# Safety.net
KiCad netlist of a schematic drawn in Altium Designer
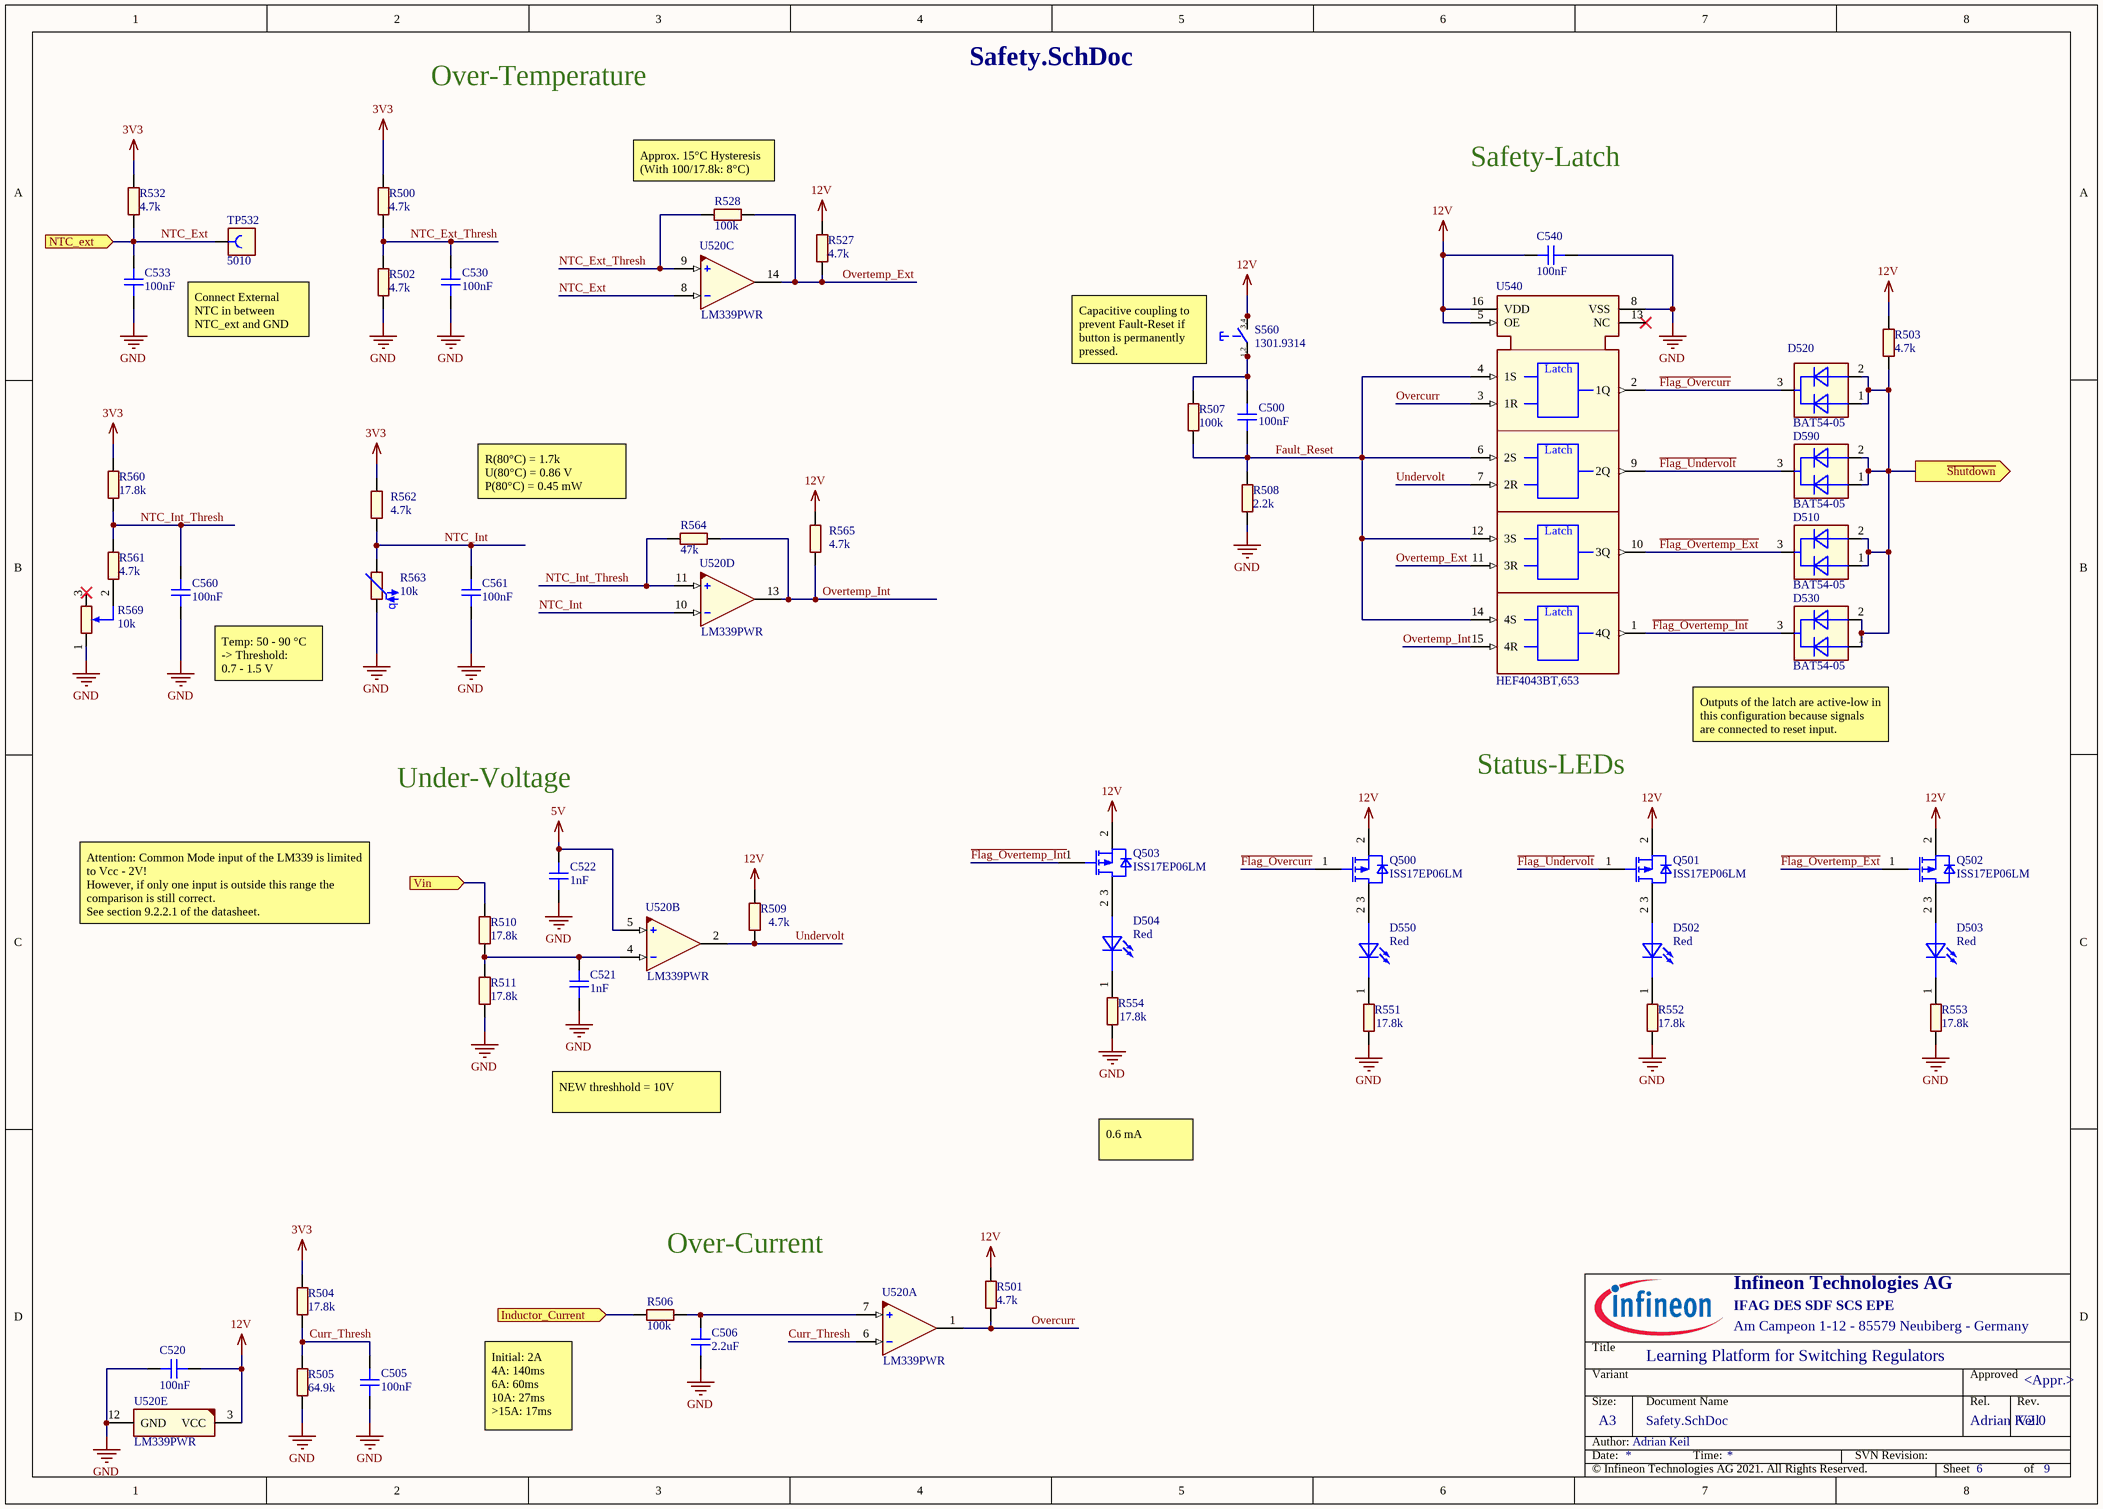
[diagram p0: Safety.SchDoc]

(export (version "E")
  (design (tool "Eeschema 10.0.6"))
  (components
    (comp (ref "C500")
      (value "100nF")
      (footprint "CAPC3216X125N-0")
      (description "CAP / CERA / 100nF / 50V / 10% / X7R (EIA) / -55°C to 125°C / 1206(3216) / SMD / -")
      (fields (field (name "LEGACY PARTNUMBER") "CAP01005660") (field (name "MANUFACTURER") "MuRata"))
      (libsource (lib "PCBLibraryData") (part "CAP-SGL-STD-02P_00000001"))
    )
    (comp (ref "C505")
      (value "100nF")
      (footprint "CAPC3216X125N-0")
      (description "CAP / CERA / 100nF / 50V / 10% / X7R (EIA) / -55°C to 125°C / 1206(3216) / SMD / -")
      (fields (field (name "LEGACY PARTNUMBER") "CAP01005660") (field (name "MANUFACTURER") "MuRata"))
      (libsource (lib "PCBLibraryData") (part "CAP-SGL-STD-02P_00000001"))
    )
    (comp (ref "C506")
      (value "2.2uF")
      (footprint "CAPC3216X70N")
      (description "CAP / CERA / 2.2uF / 25V / 10% / X5R (EIA) / -55°C to 85°C / 1206(3216) / SMD / -")
      (fields (field (name "LEGACY PARTNUMBER") "CAP01005015") (field (name "MANUFACTURER") "MuRata"))
      (libsource (lib "PCBLibraryData") (part "CAP-SGL-STD-02P_00000001"))
    )
    (comp (ref "C520")
      (value "100nF")
      (footprint "CAPC3216X125N-0")
      (description "CAP / CERA / 100nF / 50V / 10% / X7R (EIA) / -55°C to 125°C / 1206(3216) / SMD / -")
      (fields (field (name "LEGACY PARTNUMBER") "CAP01005660") (field (name "MANUFACTURER") "MuRata"))
      (libsource (lib "PCBLibraryData") (part "CAP-SGL-STD-02P_00000001"))
    )
    (comp (ref "C521")
      (value "1nF")
      (footprint "CAPC3216X95N")
      (description "CAP / CERA / 1nF / 50V / 10% / X7R (EIA) / -55°C to 125°C / 1206(3216) / SMD / -")
      (fields (field (name "LEGACY PARTNUMBER") "CAP01005183") (field (name "MANUFACTURER") "MuRata"))
      (libsource (lib "PCBLibraryData") (part "CAP-SGL-STD-02P_00000001"))
    )
    (comp (ref "C522")
      (value "1nF")
      (footprint "CAPC3216X95N")
      (description "CAP / CERA / 1nF / 50V / 10% / X7R (EIA) / -55°C to 125°C / 1206(3216) / SMD / -")
      (fields (field (name "LEGACY PARTNUMBER") "CAP01005183") (field (name "MANUFACTURER") "MuRata"))
      (libsource (lib "PCBLibraryData") (part "CAP-SGL-STD-02P_00000001"))
    )
    (comp (ref "C530")
      (value "100nF")
      (footprint "CAPC3216X125N-0")
      (description "CAP / CERA / 100nF / 50V / 10% / X7R (EIA) / -55°C to 125°C / 1206(3216) / SMD / -")
      (fields (field (name "LEGACY PARTNUMBER") "CAP01005660") (field (name "MANUFACTURER") "MuRata"))
      (libsource (lib "PCBLibraryData") (part "CAP-SGL-STD-02P_00000001"))
    )
    (comp (ref "C533")
      (value "100nF")
      (footprint "CAPC3216X125N-0")
      (description "CAP / CERA / 100nF / 50V / 10% / X7R (EIA) / -55°C to 125°C / 1206(3216) / SMD / -")
      (fields (field (name "LEGACY PARTNUMBER") "CAP01005660") (field (name "MANUFACTURER") "MuRata"))
      (libsource (lib "PCBLibraryData") (part "CAP-SGL-STD-02P_00000001"))
    )
    (comp (ref "C540")
      (value "100nF")
      (footprint "CAPC3216X125N-0")
      (description "CAP / CERA / 100nF / 50V / 10% / X7R (EIA) / -55°C to 125°C / 1206(3216) / SMD / -")
      (fields (field (name "LEGACY PARTNUMBER") "CAP01005660") (field (name "MANUFACTURER") "MuRata"))
      (libsource (lib "PCBLibraryData") (part "CAP-SGL-STD-02P_00000001"))
    )
    (comp (ref "C560")
      (value "100nF")
      (footprint "CAPC3216X125N-0")
      (description "CAP / CERA / 100nF / 50V / 10% / X7R (EIA) / -55°C to 125°C / 1206(3216) / SMD / -")
      (fields (field (name "LEGACY PARTNUMBER") "CAP01005660") (field (name "MANUFACTURER") "MuRata"))
      (libsource (lib "PCBLibraryData") (part "CAP-SGL-STD-02P_00000001"))
    )
    (comp (ref "C561")
      (value "100nF")
      (footprint "CAPC3216X125N-0")
      (description "CAP / CERA / 100nF / 50V / 10% / X7R (EIA) / -55°C to 125°C / 1206(3216) / SMD / -")
      (fields (field (name "LEGACY PARTNUMBER") "CAP01005660") (field (name "MANUFACTURER") "MuRata"))
      (libsource (lib "PCBLibraryData") (part "CAP-SGL-STD-02P_00000001"))
    )
    (comp (ref "D502")
      (value "Red")
      (footprint "LEDSC160X80X80-2N-1")
      (description "WL-SMCW SMT Mono-color Chip LED Waterclear, Red,630nm")
      (fields (field (name "MANUFACTURER") "Wurth Elektronik"))
      (libsource (lib "PCBLibraryData") (part "d_led_a"))
    )
    (comp (ref "D503")
      (value "Red")
      (footprint "LEDSC160X80X80-2N-1")
      (description "WL-SMCW SMT Mono-color Chip LED Waterclear, Red,630nm")
      (fields (field (name "MANUFACTURER") "Wurth Elektronik"))
      (libsource (lib "PCBLibraryData") (part "d_led_a"))
    )
    (comp (ref "D504")
      (value "Red")
      (footprint "LEDSC160X80X80-2N-1")
      (description "WL-SMCW SMT Mono-color Chip LED Waterclear, Red,630nm")
      (fields (field (name "MANUFACTURER") "Wurth Elektronik"))
      (libsource (lib "PCBLibraryData") (part "d_led_a"))
    )
    (comp (ref "D510")
      (value "BAT54-05")
      (footprint "SOT95P240X110-3N-1-V")
      (description "Silicon Schottky Diode, LS(nH) 1.8, VR 30V")
      (fields
        (field (name "LEGACY PARTNUMBER") "IFX01401370")
        (field (name "MANUFACTURER") "Infineon Technologies")
      )
      (libsource (lib "PCBLibraryData") (part "d_dual_a1a2c3_3p"))
    )
    (comp (ref "D520")
      (value "BAT54-05")
      (footprint "SOT95P240X110-3N-1-V")
      (description "Silicon Schottky Diode, LS(nH) 1.8, VR 30V")
      (fields
        (field (name "LEGACY PARTNUMBER") "IFX01401370")
        (field (name "MANUFACTURER") "Infineon Technologies")
      )
      (libsource (lib "PCBLibraryData") (part "d_dual_a1a2c3_3p"))
    )
    (comp (ref "D530")
      (value "BAT54-05")
      (footprint "SOT95P240X110-3N-1-V")
      (description "Silicon Schottky Diode, LS(nH) 1.8, VR 30V")
      (fields
        (field (name "LEGACY PARTNUMBER") "IFX01401370")
        (field (name "MANUFACTURER") "Infineon Technologies")
      )
      (libsource (lib "PCBLibraryData") (part "d_dual_a1a2c3_3p"))
    )
    (comp (ref "D550")
      (value "Red")
      (footprint "LEDSC160X80X80-2N-1")
      (description "WL-SMCW SMT Mono-color Chip LED Waterclear, Red,630nm")
      (fields (field (name "MANUFACTURER") "Wurth Elektronik"))
      (libsource (lib "PCBLibraryData") (part "d_led_a"))
    )
    (comp (ref "D590")
      (value "BAT54-05")
      (footprint "SOT95P240X110-3N-1-V")
      (description "Silicon Schottky Diode, LS(nH) 1.8, VR 30V")
      (fields
        (field (name "LEGACY PARTNUMBER") "IFX01401370")
        (field (name "MANUFACTURER") "Infineon Technologies")
      )
      (libsource (lib "PCBLibraryData") (part "d_dual_a1a2c3_3p"))
    )
    (comp (ref "Q500")
      (value "ISS17EP06LM")
      (footprint "SOT95P240X110-3N-1-V")
      (description "OptiMOSTM Small Signal Transistor, -60 V")
      (fields (field (name "MANUFACTURER") "Infineon Technologies"))
      (libsource (lib "PCBLibraryData") (part "igfet_p_ch_enh_dio_1g2s3d_3p"))
    )
    (comp (ref "Q501")
      (value "ISS17EP06LM")
      (footprint "SOT95P240X110-3N-1-V")
      (description "OptiMOSTM Small Signal Transistor, -60 V")
      (fields (field (name "MANUFACTURER") "Infineon Technologies"))
      (libsource (lib "PCBLibraryData") (part "igfet_p_ch_enh_dio_1g2s3d_3p"))
    )
    (comp (ref "Q502")
      (value "ISS17EP06LM")
      (footprint "SOT95P240X110-3N-1-V")
      (description "OptiMOSTM Small Signal Transistor, -60 V")
      (fields (field (name "MANUFACTURER") "Infineon Technologies"))
      (libsource (lib "PCBLibraryData") (part "igfet_p_ch_enh_dio_1g2s3d_3p"))
    )
    (comp (ref "Q503")
      (value "ISS17EP06LM")
      (footprint "SOT95P240X110-3N-1-V")
      (description "OptiMOSTM Small Signal Transistor, -60 V")
      (fields (field (name "MANUFACTURER") "Infineon Technologies"))
      (libsource (lib "PCBLibraryData") (part "igfet_p_ch_enh_dio_1g2s3d_3p"))
    )
    (comp (ref "R500")
      (value "4.7k")
      (footprint "RESC3216X60N")
      (description "RES / STD / 4.7k / 250mW / 1% / 100ppm/K / -55°C to 155°C / 1206(3216) / SMD / -")
      (fields (field (name "LEGACY PARTNUMBER") "RES01802819") (field (name "MANUFACTURER") "Vishay"))
      (libsource (lib "PCBLibraryData") (part "RES-SGL-STD-02P_00000006"))
    )
    (comp (ref "R501")
      (value "4.7k")
      (footprint "RESC3216X60N")
      (description "RES / STD / 4.7k / 250mW / 1% / 100ppm/K / -55°C to 155°C / 1206(3216) / SMD / -")
      (fields (field (name "LEGACY PARTNUMBER") "RES01802819") (field (name "MANUFACTURER") "Vishay"))
      (libsource (lib "PCBLibraryData") (part "RES-SGL-STD-02P_00000006"))
    )
    (comp (ref "R502")
      (value "4.7k")
      (footprint "RESC3216X60N")
      (description "RES / STD / 4.7k / 250mW / 1% / 100ppm/K / -55°C to 155°C / 1206(3216) / SMD / -")
      (fields (field (name "LEGACY PARTNUMBER") "RES01802819") (field (name "MANUFACTURER") "Vishay"))
      (libsource (lib "PCBLibraryData") (part "RES-SGL-STD-02P_00000006"))
    )
    (comp (ref "R503")
      (value "4.7k")
      (footprint "RESC3216X60N")
      (description "RES / STD / 4.7k / 250mW / 1% / 100ppm/K / -55°C to 155°C / 1206(3216) / SMD / -")
      (fields (field (name "LEGACY PARTNUMBER") "RES01802819") (field (name "MANUFACTURER") "Vishay"))
      (libsource (lib "PCBLibraryData") (part "RES-SGL-STD-02P_00000006"))
    )
    (comp (ref "R504")
      (value "17.8k")
      (footprint "RESC3216X60N")
      (description "RES / STD / 17.8k / 250mW / 1% / 100ppm/K / -55°C to 155°C / 1206(3216) / SMD / -")
      (fields (field (name "LEGACY PARTNUMBER") "RES01802883") (field (name "MANUFACTURER") "Vishay"))
      (libsource (lib "PCBLibraryData") (part "RES-SGL-STD-02P_00000006"))
    )
    (comp (ref "R505")
      (value "64.9k")
      (footprint "RESC3216X60N")
      (description "RES / STD / 64.9k / 250mW / 1% / 100ppm/K / -55°C to 155°C / 1206(3216) / SMD / -")
      (fields (field (name "LEGACY PARTNUMBER") "RES01802950") (field (name "MANUFACTURER") "Vishay"))
      (libsource (lib "PCBLibraryData") (part "RES-SGL-STD-02P_00000006"))
    )
    (comp (ref "R506")
      (value "100k")
      (footprint "RESC3216X60N")
      (description "RES / STD / 100k / 250mW / 1% / 100ppm/K / -55°C to 155°C / 1206(3216) / SMD / -")
      (fields (field (name "LEGACY PARTNUMBER") "RES01802971") (field (name "MANUFACTURER") "Vishay"))
      (libsource (lib "") (part "RES-SGL-STD-02P_00000006_3"))
    )
    (comp (ref "R507")
      (value "100k")
      (footprint "RESC3216X60N")
      (description "RES / STD / 100k / 250mW / 1% / 100ppm/K / -55°C to 155°C / 1206(3216) / SMD / -")
      (fields (field (name "LEGACY PARTNUMBER") "RES01802971") (field (name "MANUFACTURER") "Vishay"))
      (libsource (lib "PCBLibraryData") (part "RES-SGL-STD-02P_00000006"))
    )
    (comp (ref "R508")
      (value "2.2k")
      (footprint "RESC3216X60N")
      (description "RES / STD / 2.2k / 250mW / 1% / 100ppm/K / -55°C to 155°C / 1206(3216) / SMD / -")
      (fields (field (name "LEGACY PARTNUMBER") "RES01802779") (field (name "MANUFACTURER") "Vishay"))
      (libsource (lib "") (part "RES-SGL-STD-02P_00000006_2"))
    )
    (comp (ref "R509")
      (value "4.7k")
      (footprint "RESC3216X60N")
      (description "RES / STD / 4.7k / 250mW / 1% / 100ppm/K / -55°C to 155°C / 1206(3216) / SMD / -")
      (fields (field (name "LEGACY PARTNUMBER") "RES01802819") (field (name "MANUFACTURER") "Vishay"))
      (libsource (lib "PCBLibraryData") (part "RES-SGL-STD-02P_00000006"))
    )
    (comp (ref "R510")
      (value "17.8k")
      (footprint "RESC3216X60N")
      (description "RES / STD / 17.8k / 250mW / 1% / 100ppm/K / -55°C to 155°C / 1206(3216) / SMD / -")
      (fields (field (name "LEGACY PARTNUMBER") "RES01802883") (field (name "MANUFACTURER") "Vishay"))
      (libsource (lib "") (part "RES-SGL-STD-02P_00000006_2"))
    )
    (comp (ref "R511")
      (value "17.8k")
      (footprint "RESC3216X60N")
      (description "RES / STD / 17.8k / 250mW / 1% / 100ppm/K / -55°C to 155°C / 1206(3216) / SMD / -")
      (fields (field (name "LEGACY PARTNUMBER") "RES01802883") (field (name "MANUFACTURER") "Vishay"))
      (libsource (lib "PCBLibraryData") (part "RES-SGL-STD-02P_00000006"))
    )
    (comp (ref "R527")
      (value "4.7k")
      (footprint "RESC3216X60N")
      (description "RES / STD / 4.7k / 250mW / 1% / 100ppm/K / -55°C to 155°C / 1206(3216) / SMD / -")
      (fields (field (name "LEGACY PARTNUMBER") "RES01802819") (field (name "MANUFACTURER") "Vishay"))
      (libsource (lib "PCBLibraryData") (part "RES-SGL-STD-02P_00000006"))
    )
    (comp (ref "R528")
      (value "100k")
      (footprint "RESC3216X60N")
      (description "RES / STD / 100k / 250mW / 1% / 100ppm/K / -55°C to 155°C / 1206(3216) / SMD / -")
      (fields (field (name "LEGACY PARTNUMBER") "RES01802971") (field (name "MANUFACTURER") "Vishay"))
      (libsource (lib "") (part "RES-SGL-STD-02P_00000006_1"))
    )
    (comp (ref "R532")
      (value "4.7k")
      (footprint "RESC3216X60N")
      (description "RES / STD / 4.7k / 250mW / 1% / 100ppm/K / -55°C to 155°C / 1206(3216) / SMD / -")
      (fields (field (name "LEGACY PARTNUMBER") "RES01802819") (field (name "MANUFACTURER") "Vishay"))
      (libsource (lib "PCBLibraryData") (part "RES-SGL-STD-02P_00000006"))
    )
    (comp (ref "R551")
      (value "17.8k")
      (footprint "RESC3216X60N")
      (description "RES / STD / 17.8k / 250mW / 1% / 100ppm/K / -55°C to 155°C / 1206(3216) / SMD / -")
      (fields (field (name "LEGACY PARTNUMBER") "RES01802883") (field (name "MANUFACTURER") "Vishay"))
      (libsource (lib "") (part "RES-SGL-STD-02P_00000006_2"))
    )
    (comp (ref "R552")
      (value "17.8k")
      (footprint "RESC3216X60N")
      (description "RES / STD / 17.8k / 250mW / 1% / 100ppm/K / -55°C to 155°C / 1206(3216) / SMD / -")
      (fields (field (name "LEGACY PARTNUMBER") "RES01802883") (field (name "MANUFACTURER") "Vishay"))
      (libsource (lib "PCBLibraryData") (part "RES-SGL-STD-02P_00000006"))
    )
    (comp (ref "R553")
      (value "17.8k")
      (footprint "RESC3216X60N")
      (description "RES / STD / 17.8k / 250mW / 1% / 100ppm/K / -55°C to 155°C / 1206(3216) / SMD / -")
      (fields (field (name "LEGACY PARTNUMBER") "RES01802883") (field (name "MANUFACTURER") "Vishay"))
      (libsource (lib "PCBLibraryData") (part "RES-SGL-STD-02P_00000006"))
    )
    (comp (ref "R554")
      (value "17.8k")
      (footprint "RESC3216X60N")
      (description "RES / STD / 17.8k / 250mW / 1% / 100ppm/K / -55°C to 155°C / 1206(3216) / SMD / -")
      (fields (field (name "LEGACY PARTNUMBER") "RES01802883") (field (name "MANUFACTURER") "Vishay"))
      (libsource (lib "") (part "RES-SGL-STD-02P_00000006_2"))
    )
    (comp (ref "R560")
      (value "17.8k")
      (footprint "RESC3216X60N")
      (description "RES / STD / 17.8k / 250mW / 1% / 100ppm/K / -55°C to 155°C / 1206(3216) / SMD / -")
      (fields (field (name "LEGACY PARTNUMBER") "RES01802883") (field (name "MANUFACTURER") "Vishay"))
      (libsource (lib "") (part "RES-SGL-STD-02P_00000006_2"))
    )
    (comp (ref "R561")
      (value "4.7k")
      (footprint "RESC3216X60N")
      (description "RES / STD / 4.7k / 250mW / 1% / 100ppm/K / -55°C to 155°C / 1206(3216) / SMD / -")
      (fields (field (name "LEGACY PARTNUMBER") "RES01802819") (field (name "MANUFACTURER") "Vishay"))
      (libsource (lib "PCBLibraryData") (part "RES-SGL-STD-02P_00000006"))
    )
    (comp (ref "R562")
      (value "4.7k")
      (footprint "RESC3216X60N")
      (description "RES / STD / 4.7k / 250mW / 1% / 100ppm/K / -55°C to 155°C / 1206(3216) / SMD / -")
      (fields (field (name "LEGACY PARTNUMBER") "RES01802819") (field (name "MANUFACTURER") "Vishay"))
      (libsource (lib "PCBLibraryData") (part "RES-SGL-STD-02P_00000006"))
    )
    (comp (ref "R563")
      (value "10k")
      (footprint "RESC1608X95N-1")
      (description "RES / NTC / 10k / 100mW / 1% / - / -40°C to 125°C / 0603(1608) / SMD / -")
      (fields (field (name "LEGACY PARTNUMBER") "RES01806219") (field (name "MANUFACTURER") "MuRata"))
      (libsource (lib "PCBLibraryData") (part "RES-SGL-NTC-02P_00000007"))
    )
    (comp (ref "R564")
      (value "47k")
      (footprint "RESC3216X60N")
      (description "RES / STD / 47k / 250mW / 1% / 100ppm/K / -55°C to 155°C / 1206(3216) / SMD / -")
      (fields (field (name "LEGACY PARTNUMBER") "RES01802933") (field (name "MANUFACTURER") "Vishay"))
      (libsource (lib "") (part "RES-SGL-STD-02P_00000006_1"))
    )
    (comp (ref "R565")
      (value "4.7k")
      (footprint "RESC3216X60N")
      (description "RES / STD / 4.7k / 250mW / 1% / 100ppm/K / -55°C to 155°C / 1206(3216) / SMD / -")
      (fields (field (name "LEGACY PARTNUMBER") "RES01802819") (field (name "MANUFACTURER") "Vishay"))
      (libsource (lib "PCBLibraryData") (part "RES-SGL-STD-02P_00000006"))
    )
    (comp (ref "R569")
      (value "10k")
      (footprint "POT-SMD-3361P")
      (fields (field (name "MANUFACTURER") "Bourns"))
      (libsource (lib "PCBLibraryData") (part "RES-SGL-VAR-03P_00000026"))
    )
    (comp (ref "S560")
      (value "1301.9314")
      (footprint "SW-SMD-1301.9314")
      (description "Pushbutton Tactile Switch, Single Pole Single Throw, 4 Pins")
      (fields (field (name "LEGACY PARTNUMBER") "CON01500305") (field (name "MANUFACTURER") "Schurter"))
      (libsource (lib "PCBLibraryData") (part "sw_sr_no12_34_4p"))
    )
    (comp (ref "TP532")
      (value "5010")
      (footprint "CON-THT-TP-5010")
      (description "PC Test Point-Multipurpose THT, Red")
      (fields
        (field (name "LEGACY PARTNUMBER") "CON01500529")
        (field (name "MANUFACTURER") "Keystone Electronics Corp.")
      )
      (libsource (lib "PCBLibraryData") (part "connector_1_f"))
    )
    (comp (ref "U520")
      (value "LM339PWR")
      (footprint "SOP65P640X120-14N-1")
      (description "Quad Differential Comparator")
      (fields
        (field (name "LEGACY PARTNUMBER") "IC02600564")
        (field (name "MANUFACTURER") "Texas Instruments")
      )
      (libsource (lib "PCBLibraryData") (part "LM339PWR"))
    )
    (comp (ref "U540")
      (value "HEF4043BT,653")
      (footprint "SOIC127P600X175-16N-6")
      (description "Quad R/S latch with 3-state outputs")
      (fields (field (name "MANUFACTURER") "Nexperia"))
      (libsource (lib "PCBLibraryData") (part "HEF4043B"))
    )
  )
  (nets
    (net (code "1") (name "/Curr_Thresh") (class "Default")
      (node (ref "C505") (pin "2") (pinfunction "2_2") (pintype "passive"))
      (node (ref "R504") (pin "1") (pinfunction "1_1") (pintype "passive"))
      (node (ref "R505") (pin "2") (pinfunction "2_2") (pintype "passive"))
      (node (ref "U520") (pin "6") (pinfunction "1IN_N_6") (pintype "input"))
    )
    (net (code "2") (name "/Fault_Reset") (class "Default")
      (node (ref "C500") (pin "2") (pinfunction "2_2") (pintype "passive"))
      (node (ref "R507") (pin "1") (pinfunction "1_1") (pintype "passive"))
      (node (ref "R508") (pin "1") (pinfunction "1_1") (pintype "passive"))
      (node (ref "U540") (pin "12") (pinfunction "3S_12") (pintype "input"))
      (node (ref "U540") (pin "14") (pinfunction "4S_14") (pintype "input"))
      (node (ref "U540") (pin "4") (pinfunction "1S_4") (pintype "input"))
      (node (ref "U540") (pin "6") (pinfunction "2S_6") (pintype "input"))
    )
    (net (code "3") (name "/Flag_Overcurr") (class "Default")
      (node (ref "D520") (pin "3") (pinfunction "CATHODE_3") (pintype "passive"))
      (node (ref "Q500") (pin "1") (pinfunction "GATE_1") (pintype "passive"))
      (node (ref "U540") (pin "2") (pinfunction "1Q_2") (pintype "output"))
    )
    (net (code "4") (name "/Flag_Overtemp_Ext") (class "Default")
      (node (ref "D510") (pin "3") (pinfunction "CATHODE_3") (pintype "passive"))
      (node (ref "Q502") (pin "1") (pinfunction "GATE_1") (pintype "passive"))
      (node (ref "U540") (pin "10") (pinfunction "3Q_10") (pintype "output"))
    )
    (net (code "5") (name "/Flag_Overtemp_Int") (class "Default")
      (node (ref "D530") (pin "3") (pinfunction "CATHODE_3") (pintype "passive"))
      (node (ref "Q503") (pin "1") (pinfunction "GATE_1") (pintype "passive"))
      (node (ref "U540") (pin "1") (pinfunction "4Q_1") (pintype "output"))
    )
    (net (code "6") (name "/Flag_Undervolt") (class "Default")
      (node (ref "D590") (pin "3") (pinfunction "CATHODE_3") (pintype "passive"))
      (node (ref "Q501") (pin "1") (pinfunction "GATE_1") (pintype "passive"))
      (node (ref "U540") (pin "9") (pinfunction "2Q_9") (pintype "output"))
    )
    (net (code "7") (name "/Inductor_Current") (class "Default")
      (node (ref "R506") (pin "1") (pinfunction "1_1") (pintype "passive"))
    )
    (net (code "8") (name "/NTC_Ext") (class "Default")
      (node (ref "C533") (pin "2") (pinfunction "2_2") (pintype "passive"))
      (node (ref "R532") (pin "1") (pinfunction "1_1") (pintype "passive"))
      (node (ref "TP532") (pin "1") (pinfunction "1_1") (pintype "passive"))
      (node (ref "U520") (pin "8") (pinfunction "3IN_N_8") (pintype "input"))
    )
    (net (code "9") (name "/NTC_Ext_Thresh") (class "Default")
      (node (ref "C530") (pin "2") (pinfunction "2_2") (pintype "passive"))
      (node (ref "R500") (pin "1") (pinfunction "1_1") (pintype "passive"))
      (node (ref "R502") (pin "2") (pinfunction "2_2") (pintype "passive"))
      (node (ref "R528") (pin "2") (pinfunction "2_2") (pintype "passive"))
      (node (ref "U520") (pin "9") (pinfunction "3IN_P_9") (pintype "input"))
    )
    (net (code "10") (name "/NTC_Int") (class "Default")
      (node (ref "C561") (pin "2") (pinfunction "2_2") (pintype "passive"))
      (node (ref "R562") (pin "1") (pinfunction "1_1") (pintype "passive"))
      (node (ref "R563") (pin "2") (pinfunction "2_2") (pintype "passive"))
      (node (ref "U520") (pin "10") (pinfunction "4IN_N_10") (pintype "input"))
    )
    (net (code "11") (name "/NTC_Int_Thresh") (class "Default")
      (node (ref "C560") (pin "2") (pinfunction "2_2") (pintype "passive"))
      (node (ref "R560") (pin "2") (pinfunction "2_2") (pintype "passive"))
      (node (ref "R561") (pin "2") (pinfunction "2_2") (pintype "passive"))
      (node (ref "R564") (pin "2") (pinfunction "2_2") (pintype "passive"))
      (node (ref "U520") (pin "11") (pinfunction "4IN_P_11") (pintype "input"))
    )
    (net (code "12") (name "/Overcurr") (class "Default")
      (node (ref "R501") (pin "1") (pinfunction "1_1") (pintype "passive"))
      (node (ref "U520") (pin "1") (pinfunction "1OUT_1") (pintype "open_collector"))
      (node (ref "U540") (pin "3") (pinfunction "1R_3") (pintype "input"))
    )
    (net (code "13") (name "/Overtemp_Ext") (class "Default")
      (node (ref "R527") (pin "1") (pinfunction "1_1") (pintype "passive"))
      (node (ref "R528") (pin "1") (pinfunction "1_1") (pintype "passive"))
      (node (ref "U520") (pin "14") (pinfunction "3OUT_14") (pintype "open_collector"))
      (node (ref "U540") (pin "11") (pinfunction "3R_11") (pintype "input"))
    )
    (net (code "14") (name "/Overtemp_Int") (class "Default")
      (node (ref "R564") (pin "1") (pinfunction "1_1") (pintype "passive"))
      (node (ref "R565") (pin "1") (pinfunction "1_1") (pintype "passive"))
      (node (ref "U520") (pin "13") (pinfunction "4OUT_13") (pintype "open_collector"))
      (node (ref "U540") (pin "15") (pinfunction "4R_15") (pintype "input"))
    )
    (net (code "15") (name "/Shutdown") (class "Default")
      (node (ref "D510") (pin "1") (pinfunction "ANODE_1_1") (pintype "passive"))
      (node (ref "D510") (pin "2") (pinfunction "ANODE_2_2") (pintype "passive"))
      (node (ref "D520") (pin "1") (pinfunction "ANODE_1_1") (pintype "passive"))
      (node (ref "D520") (pin "2") (pinfunction "ANODE_2_2") (pintype "passive"))
      (node (ref "D530") (pin "1") (pinfunction "ANODE_1_1") (pintype "passive"))
      (node (ref "D530") (pin "2") (pinfunction "ANODE_2_2") (pintype "passive"))
      (node (ref "D590") (pin "1") (pinfunction "ANODE_1_1") (pintype "passive"))
      (node (ref "D590") (pin "2") (pinfunction "ANODE_2_2") (pintype "passive"))
      (node (ref "R503") (pin "1") (pinfunction "1_1") (pintype "passive"))
    )
    (net (code "16") (name "/Undervolt") (class "Default")
      (node (ref "R509") (pin "1") (pinfunction "1_1") (pintype "passive"))
      (node (ref "U520") (pin "2") (pinfunction "2OUT_2") (pintype "open_collector"))
      (node (ref "U540") (pin "7") (pinfunction "2R_7") (pintype "input"))
    )
    (net (code "17") (name "/Vin") (class "Default")
      (node (ref "R510") (pin "1") (pinfunction "1_1") (pintype "passive"))
    )
    (net (code "18") (name "3V3") (class "Default")
      (node (ref "R500") (pin "2") (pinfunction "2_2") (pintype "passive"))
      (node (ref "R504") (pin "2") (pinfunction "2_2") (pintype "passive"))
      (node (ref "R532") (pin "2") (pinfunction "2_2") (pintype "passive"))
      (node (ref "R560") (pin "1") (pinfunction "1_1") (pintype "passive"))
      (node (ref "R562") (pin "2") (pinfunction "2_2") (pintype "passive"))
    )
    (net (code "19") (name "5V") (class "Default")
      (node (ref "C522") (pin "2") (pinfunction "2_2") (pintype "passive"))
      (node (ref "U520") (pin "5") (pinfunction "2IN_P_5") (pintype "input"))
    )
    (net (code "20") (name "12V") (class "Default")
      (node (ref "C520") (pin "1") (pinfunction "1_1") (pintype "passive"))
      (node (ref "C540") (pin "2") (pinfunction "2_2") (pintype "passive"))
      (node (ref "Q500") (pin "2") (pinfunction "SOURCE_2") (pintype "passive"))
      (node (ref "Q501") (pin "2") (pinfunction "SOURCE_2") (pintype "passive"))
      (node (ref "Q502") (pin "2") (pinfunction "SOURCE_2") (pintype "passive"))
      (node (ref "Q503") (pin "2") (pinfunction "SOURCE_2") (pintype "passive"))
      (node (ref "R501") (pin "2") (pinfunction "2_2") (pintype "passive"))
      (node (ref "R503") (pin "2") (pinfunction "2_2") (pintype "passive"))
      (node (ref "R509") (pin "2") (pinfunction "2_2") (pintype "passive"))
      (node (ref "R527") (pin "2") (pinfunction "2_2") (pintype "passive"))
      (node (ref "R565") (pin "2") (pinfunction "2_2") (pintype "passive"))
      (node (ref "S560") (pin "3") (pinfunction "3_3") (pintype "passive"))
      (node (ref "S560") (pin "4") (pinfunction "4_4") (pintype "passive"))
      (node (ref "U520") (pin "3") (pinfunction "VCC_3") (pintype "power_in"))
      (node (ref "U540") (pin "16") (pinfunction "VDD_16") (pintype "power_in"))
      (node (ref "U540") (pin "5") (pinfunction "OE_5") (pintype "input"))
    )
    (net (code "21") (name "GND") (class "Default")
      (node (ref "C505") (pin "1") (pinfunction "1_1") (pintype "passive"))
      (node (ref "C506") (pin "1") (pinfunction "1_1") (pintype "passive"))
      (node (ref "C520") (pin "2") (pinfunction "2_2") (pintype "passive"))
      (node (ref "C521") (pin "1") (pinfunction "1_1") (pintype "passive"))
      (node (ref "C522") (pin "1") (pinfunction "1_1") (pintype "passive"))
      (node (ref "C530") (pin "1") (pinfunction "1_1") (pintype "passive"))
      (node (ref "C533") (pin "1") (pinfunction "1_1") (pintype "passive"))
      (node (ref "C540") (pin "1") (pinfunction "1_1") (pintype "passive"))
      (node (ref "C560") (pin "1") (pinfunction "1_1") (pintype "passive"))
      (node (ref "C561") (pin "1") (pinfunction "1_1") (pintype "passive"))
      (node (ref "R502") (pin "1") (pinfunction "1_1") (pintype "passive"))
      (node (ref "R505") (pin "1") (pinfunction "1_1") (pintype "passive"))
      (node (ref "R508") (pin "2") (pinfunction "2_2") (pintype "passive"))
      (node (ref "R511") (pin "1") (pinfunction "1_1") (pintype "passive"))
      (node (ref "R551") (pin "2") (pinfunction "2_2") (pintype "passive"))
      (node (ref "R552") (pin "1") (pinfunction "1_1") (pintype "passive"))
      (node (ref "R553") (pin "1") (pinfunction "1_1") (pintype "passive"))
      (node (ref "R554") (pin "2") (pinfunction "2_2") (pintype "passive"))
      (node (ref "R563") (pin "1") (pinfunction "1_1") (pintype "passive"))
      (node (ref "R569") (pin "1") (pinfunction "1_1") (pintype "passive"))
      (node (ref "U520") (pin "12") (pinfunction "GND_12") (pintype "power_in"))
      (node (ref "U540") (pin "8") (pinfunction "VSS_8") (pintype "power_in"))
    )
    (net (code "22") (name "Net-(C500-Pad1)") (class "Default")
      (node (ref "C500") (pin "1") (pinfunction "1_1") (pintype "passive"))
      (node (ref "R507") (pin "2") (pinfunction "2_2") (pintype "passive"))
      (node (ref "S560") (pin "1") (pinfunction "1_1") (pintype "passive"))
      (node (ref "S560") (pin "2") (pinfunction "2_2") (pintype "passive"))
    )
    (net (code "23") (name "Net-(D502-Anode)") (class "Default")
      (node (ref "D502") (pin "2") (pinfunction "Anode_2") (pintype "passive"))
      (node (ref "Q501") (pin "3") (pinfunction "DRAIN_3") (pintype "passive"))
    )
    (net (code "24") (name "Net-(D502-Cathode)") (class "Default")
      (node (ref "D502") (pin "1") (pinfunction "Cathode_1") (pintype "passive"))
      (node (ref "R552") (pin "2") (pinfunction "2_2") (pintype "passive"))
    )
    (net (code "25") (name "Net-(D503-Anode)") (class "Default")
      (node (ref "D503") (pin "2") (pinfunction "Anode_2") (pintype "passive"))
      (node (ref "Q502") (pin "3") (pinfunction "DRAIN_3") (pintype "passive"))
    )
    (net (code "26") (name "Net-(D503-Cathode)") (class "Default")
      (node (ref "D503") (pin "1") (pinfunction "Cathode_1") (pintype "passive"))
      (node (ref "R553") (pin "2") (pinfunction "2_2") (pintype "passive"))
    )
    (net (code "27") (name "Net-(D504-Anode)") (class "Default")
      (node (ref "D504") (pin "2") (pinfunction "Anode_2") (pintype "passive"))
      (node (ref "Q503") (pin "3") (pinfunction "DRAIN_3") (pintype "passive"))
    )
    (net (code "28") (name "Net-(D504-Cathode)") (class "Default")
      (node (ref "D504") (pin "1") (pinfunction "Cathode_1") (pintype "passive"))
      (node (ref "R554") (pin "1") (pinfunction "1_1") (pintype "passive"))
    )
    (net (code "29") (name "Net-(D550-Anode)") (class "Default")
      (node (ref "D550") (pin "2") (pinfunction "Anode_2") (pintype "passive"))
      (node (ref "Q500") (pin "3") (pinfunction "DRAIN_3") (pintype "passive"))
    )
    (net (code "30") (name "Net-(D550-Cathode)") (class "Default")
      (node (ref "D550") (pin "1") (pinfunction "Cathode_1") (pintype "passive"))
      (node (ref "R551") (pin "1") (pinfunction "1_1") (pintype "passive"))
    )
    (net (code "31") (name "Net-(R561-Pad1)") (class "Default")
      (node (ref "R561") (pin "1") (pinfunction "1_1") (pintype "passive"))
      (node (ref "R569") (pin "2") (pinfunction "2_2") (pintype "passive"))
    )
    (net (code "32") (name "Net-(U520A-1IN_P)") (class "Default")
      (node (ref "C506") (pin "2") (pinfunction "2_2") (pintype "passive"))
      (node (ref "R506") (pin "2") (pinfunction "2_2") (pintype "passive"))
      (node (ref "U520") (pin "7") (pinfunction "1IN_P_7") (pintype "input"))
    )
    (net (code "33") (name "Net-(U520B-2IN_N)") (class "Default")
      (node (ref "C521") (pin "2") (pinfunction "2_2") (pintype "passive"))
      (node (ref "R510") (pin "2") (pinfunction "2_2") (pintype "passive"))
      (node (ref "R511") (pin "2") (pinfunction "2_2") (pintype "passive"))
      (node (ref "U520") (pin "4") (pinfunction "2IN_N_4") (pintype "input"))
    )
    (net (code "34") (name "unconnected-(R569-Pad3)") (class "Default")
      (node (ref "R569") (pin "3") (pinfunction "3_3") (pintype "passive+no_connect"))
    )
    (net (code "35") (name "unconnected-(U540-NC-Pad13)") (class "Default")
      (node (ref "U540") (pin "13") (pinfunction "NC_13") (pintype "passive+no_connect"))
    )
  )
)
